# Power_Tail_Breakout.net
KiCad netlist of a schematic drawn in EAGLE
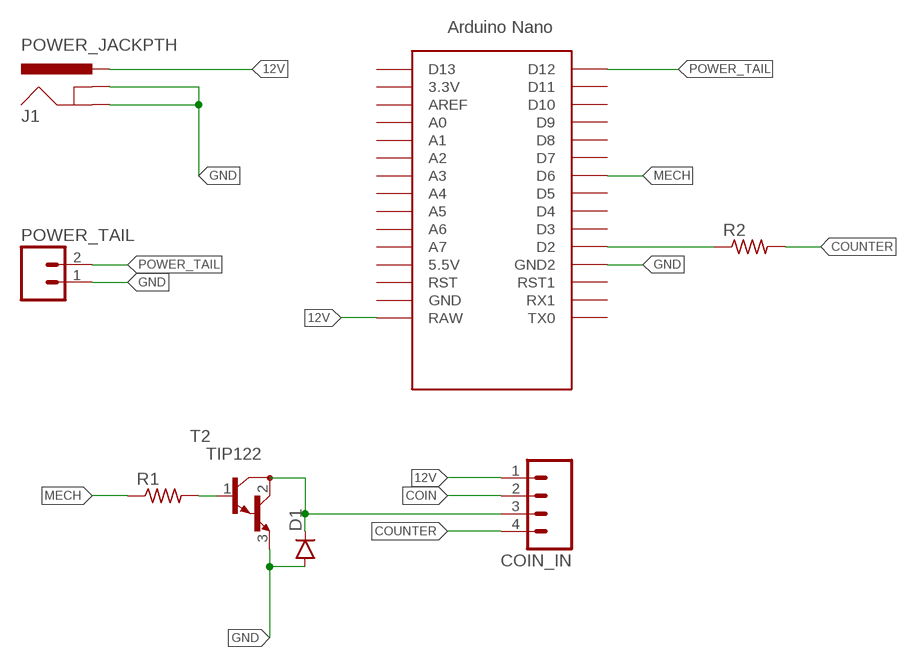
[diagram p0: schematic, sheet 1]

(export (version "E")
  (design (tool "Eeschema 10.0.6"))
  (components
    (comp (ref "COIN_IN")
      (value "M041X04_NO_SILK")
      (footprint "eagle-import:1X04_NO_SILK")
      (libsource (lib "eagle-import") (part "M041X04_NO_SILK"))
    )
    (comp (ref "D1")
      (value "DIODEPTH")
      (footprint "eagle-import:DIODE-1N4001")
      (libsource (lib "eagle-import") (part "DIODEPTH"))
    )
    (comp (ref "J1")
      (value "POWER_JACKPTH")
      (footprint "eagle-import:POWER_JACK_PTH")
      (libsource (lib "eagle-import") (part "POWER_JACKPTH"))
    )
    (comp (ref "POWER_TAIL")
      (value "M02LOCK_LONGPADS")
      (footprint "eagle-import:1X02_LOCK_LONGPADS")
      (libsource (lib "eagle-import") (part "M02LOCK_LONGPADS"))
    )
    (comp (ref "R1")
      (value "R-US_0411/3V")
      (footprint "eagle-import:0411V")
      (libsource (lib "eagle-import") (part "R-US_0411/3V"))
    )
    (comp (ref "R2")
      (value "R-US_0411/3V")
      (footprint "eagle-import:0411V")
      (libsource (lib "eagle-import") (part "R-US_0411/3V"))
    )
    (comp (ref "T2")
      (value "TIP122")
      (footprint "eagle-import:TO220")
      (libsource (lib "eagle-import") (part "TIP122"))
    )
    (comp (ref "U$1")
      (value "NANO")
      (footprint "eagle-import:NANO")
      (libsource (lib "eagle-import") (part "NANO"))
    )
  )
  (nets
    (net (code "1") (name "12V") (class "Default")
      (node (ref "COIN_IN") (pin "1") (pinfunction "1_1") (pintype "passive"))
      (node (ref "J1") (pin "PWR") (pinfunction "PWR_PWR") (pintype "bidirectional"))
      (node (ref "U$1") (pin "RAW") (pinfunction "RAW_RAW") (pintype "bidirectional"))
    )
    (net (code "2") (name "COIN") (class "Default")
      (node (ref "COIN_IN") (pin "2") (pinfunction "2_2") (pintype "passive"))
    )
    (net (code "3") (name "COUNTER") (class "Default")
      (node (ref "COIN_IN") (pin "4") (pinfunction "4_4") (pintype "passive"))
      (node (ref "R2") (pin "2") (pinfunction "2_2") (pintype "passive"))
    )
    (net (code "4") (name "GND") (class "Default")
      (node (ref "D1") (pin "A") (pinfunction "A_A") (pintype "passive"))
      (node (ref "J1") (pin "GND") (pinfunction "GND_GND") (pintype "bidirectional"))
      (node (ref "J1") (pin "GNDBREAK") (pinfunction "GNDBREAK_GNDBREAK") (pintype "bidirectional"))
      (node (ref "POWER_TAIL") (pin "1") (pinfunction "1_1") (pintype "passive"))
      (node (ref "T2") (pin "3") (pinfunction "E_3") (pintype "passive"))
      (node (ref "U$1") (pin "GND1") (pinfunction "GND2_GND1") (pintype "bidirectional"))
    )
    (net (code "5") (name "MECH") (class "Default")
      (node (ref "R1") (pin "1") (pinfunction "1_1") (pintype "passive"))
      (node (ref "U$1") (pin "D6") (pinfunction "D6_D6") (pintype "bidirectional"))
    )
    (net (code "6") (name "Net-(R2-Pad1)") (class "Default")
      (node (ref "R2") (pin "1") (pinfunction "1_1") (pintype "passive"))
      (node (ref "U$1") (pin "D2") (pinfunction "D2_D2") (pintype "bidirectional"))
    )
    (net (code "7") (name "Net-(T2-B)") (class "Default")
      (node (ref "R1") (pin "2") (pinfunction "2_2") (pintype "passive"))
      (node (ref "T2") (pin "1") (pinfunction "B_1") (pintype "passive"))
    )
    (net (code "8") (name "Net-(T2-C)") (class "Default")
      (node (ref "COIN_IN") (pin "3") (pinfunction "3_3") (pintype "passive"))
      (node (ref "D1") (pin "C") (pinfunction "C_C") (pintype "passive"))
      (node (ref "T2") (pin "2") (pinfunction "C_2") (pintype "passive"))
    )
    (net (code "9") (name "POWER_TAIL") (class "Default")
      (node (ref "POWER_TAIL") (pin "2") (pinfunction "2_2") (pintype "passive"))
      (node (ref "U$1") (pin "D12") (pinfunction "D12_D12") (pintype "bidirectional"))
    )
    (net (code "10") (name "unconnected-(U$1-5.5V-Pad5V)") (class "Default")
      (node (ref "U$1") (pin "5V") (pinfunction "5.5V_5V") (pintype "bidirectional"))
    )
    (net (code "11") (name "unconnected-(U$1-Pad3.3V)") (class "Default")
      (node (ref "U$1") (pin "3.3V") (pinfunction "3.3V_3.3V") (pintype "bidirectional"))
    )
    (net (code "12") (name "unconnected-(U$1-PadA0)") (class "Default")
      (node (ref "U$1") (pin "A0") (pinfunction "A0_A0") (pintype "bidirectional"))
    )
    (net (code "13") (name "unconnected-(U$1-PadA1)") (class "Default")
      (node (ref "U$1") (pin "A1") (pinfunction "A1_A1") (pintype "bidirectional"))
    )
    (net (code "14") (name "unconnected-(U$1-PadA2)") (class "Default")
      (node (ref "U$1") (pin "A2") (pinfunction "A2_A2") (pintype "bidirectional"))
    )
    (net (code "15") (name "unconnected-(U$1-PadA3)") (class "Default")
      (node (ref "U$1") (pin "A3") (pinfunction "A3_A3") (pintype "bidirectional"))
    )
    (net (code "16") (name "unconnected-(U$1-PadA4)") (class "Default")
      (node (ref "U$1") (pin "A4") (pinfunction "A4_A4") (pintype "bidirectional"))
    )
    (net (code "17") (name "unconnected-(U$1-PadA5)") (class "Default")
      (node (ref "U$1") (pin "A5") (pinfunction "A5_A5") (pintype "bidirectional"))
    )
    (net (code "18") (name "unconnected-(U$1-PadA6)") (class "Default")
      (node (ref "U$1") (pin "A6") (pinfunction "A6_A6") (pintype "bidirectional"))
    )
    (net (code "19") (name "unconnected-(U$1-PadA7)") (class "Default")
      (node (ref "U$1") (pin "A7") (pinfunction "A7_A7") (pintype "bidirectional"))
    )
    (net (code "20") (name "unconnected-(U$1-PadAREF)") (class "Default")
      (node (ref "U$1") (pin "AREF") (pinfunction "AREF_AREF") (pintype "bidirectional"))
    )
    (net (code "21") (name "unconnected-(U$1-PadD3)") (class "Default")
      (node (ref "U$1") (pin "D3") (pinfunction "D3_D3") (pintype "bidirectional"))
    )
    (net (code "22") (name "unconnected-(U$1-PadD4)") (class "Default")
      (node (ref "U$1") (pin "D4") (pinfunction "D4_D4") (pintype "bidirectional"))
    )
    (net (code "23") (name "unconnected-(U$1-PadD5)") (class "Default")
      (node (ref "U$1") (pin "D5") (pinfunction "D5_D5") (pintype "bidirectional"))
    )
    (net (code "24") (name "unconnected-(U$1-PadD7)") (class "Default")
      (node (ref "U$1") (pin "D7") (pinfunction "D7_D7") (pintype "bidirectional"))
    )
    (net (code "25") (name "unconnected-(U$1-PadD8)") (class "Default")
      (node (ref "U$1") (pin "D8") (pinfunction "D8_D8") (pintype "bidirectional"))
    )
    (net (code "26") (name "unconnected-(U$1-PadD9)") (class "Default")
      (node (ref "U$1") (pin "D9") (pinfunction "D9_D9") (pintype "bidirectional"))
    )
    (net (code "27") (name "unconnected-(U$1-PadD10)") (class "Default")
      (node (ref "U$1") (pin "D10") (pinfunction "D10_D10") (pintype "bidirectional"))
    )
    (net (code "28") (name "unconnected-(U$1-PadD11)") (class "Default")
      (node (ref "U$1") (pin "D11") (pinfunction "D11_D11") (pintype "bidirectional"))
    )
    (net (code "29") (name "unconnected-(U$1-PadD13)") (class "Default")
      (node (ref "U$1") (pin "D13") (pinfunction "D13_D13") (pintype "bidirectional"))
    )
    (net (code "30") (name "unconnected-(U$1-PadGND)") (class "Default")
      (node (ref "U$1") (pin "GND") (pinfunction "GND_GND") (pintype "bidirectional"))
    )
    (net (code "31") (name "unconnected-(U$1-PadICSP1)") (class "Default")
      (node (ref "U$1") (pin "ICSP1") (pinfunction "ICSP1_ICSP1") (pintype "bidirectional"))
    )
    (net (code "32") (name "unconnected-(U$1-PadICSP2)") (class "Default")
      (node (ref "U$1") (pin "ICSP2") (pinfunction "ICSP2_ICSP2") (pintype "bidirectional"))
    )
    (net (code "33") (name "unconnected-(U$1-PadICSP3)") (class "Default")
      (node (ref "U$1") (pin "ICSP3") (pinfunction "ICSP3_ICSP3") (pintype "bidirectional"))
    )
    (net (code "34") (name "unconnected-(U$1-PadICSP4)") (class "Default")
      (node (ref "U$1") (pin "ICSP4") (pinfunction "ICSP4_ICSP4") (pintype "bidirectional"))
    )
    (net (code "35") (name "unconnected-(U$1-PadICSP5)") (class "Default")
      (node (ref "U$1") (pin "ICSP5") (pinfunction "ICSP5_ICSP5") (pintype "bidirectional"))
    )
    (net (code "36") (name "unconnected-(U$1-PadICSP6)") (class "Default")
      (node (ref "U$1") (pin "ICSP6") (pinfunction "ICSP6_ICSP6") (pintype "bidirectional"))
    )
    (net (code "37") (name "unconnected-(U$1-PadRST)") (class "Default")
      (node (ref "U$1") (pin "RST") (pinfunction "RST_RST") (pintype "bidirectional"))
    )
    (net (code "38") (name "unconnected-(U$1-PadRST1)") (class "Default")
      (node (ref "U$1") (pin "RST1") (pinfunction "RST1_RST1") (pintype "bidirectional"))
    )
    (net (code "39") (name "unconnected-(U$1-PadRX1)") (class "Default")
      (node (ref "U$1") (pin "RX1") (pinfunction "RX1_RX1") (pintype "bidirectional"))
    )
    (net (code "40") (name "unconnected-(U$1-PadTX0)") (class "Default")
      (node (ref "U$1") (pin "TX0") (pinfunction "TX0_TX0") (pintype "bidirectional"))
    )
  )
)
